# YouHaveBeenBlinded.net
KiCad netlist of a schematic drawn in EAGLE
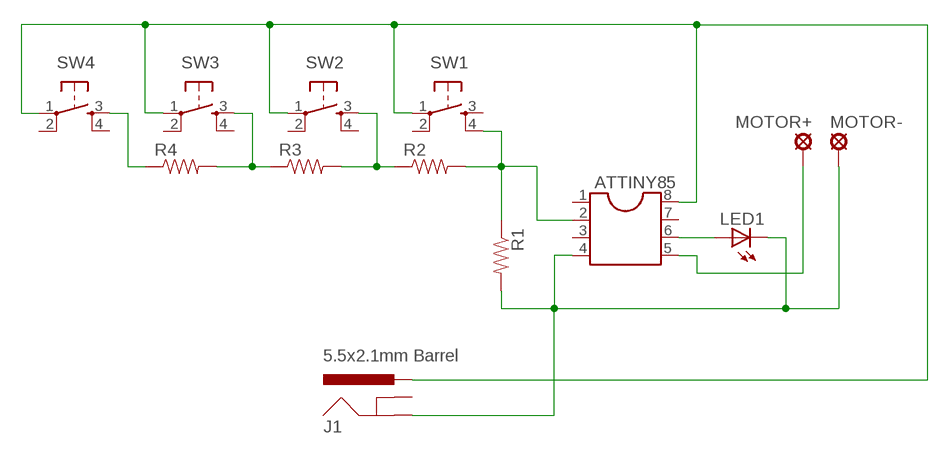
[diagram p0: schematic, sheet 1]

(export (version "E")
  (design (tool "Eeschema 10.0.6"))
  (components
    (comp (ref "ATTINY85")
      (value "DIL8S")
      (footprint "eagle-import:SOCKET-08")
      (libsource (lib "eagle-import") (part "DIL8S"))
    )
    (comp (ref "J1")
      (value "5.5x2.1mm Barrel")
      (footprint "eagle-import:POWER_JACK_SMD")
      (libsource (lib "eagle-import") (part "POWER_JACKSMD"))
    )
    (comp (ref "LED1")
      (value "LEDCHIPLED_0805")
      (footprint "eagle-import:CHIPLED_0805")
      (libsource (lib "eagle-import") (part "LEDCHIPLED_0805"))
    )
    (comp (ref "MOTOR+")
      (value "LSP10")
      (footprint "eagle-import:LSP10")
      (libsource (lib "eagle-import") (part "LSP10"))
    )
    (comp (ref "MOTOR-")
      (value "LSP10")
      (footprint "eagle-import:LSP10")
      (libsource (lib "eagle-import") (part "LSP10"))
    )
    (comp (ref "R1")
      (value "RESISTOR2010")
      (footprint "eagle-import:R2010")
      (libsource (lib "eagle-import") (part "RESISTOR2010"))
    )
    (comp (ref "R2")
      (value "RESISTOR2010")
      (footprint "eagle-import:R2010")
      (libsource (lib "eagle-import") (part "RESISTOR2010"))
    )
    (comp (ref "R3")
      (value "RESISTOR2010")
      (footprint "eagle-import:R2010")
      (libsource (lib "eagle-import") (part "RESISTOR2010"))
    )
    (comp (ref "R4")
      (value "RESISTOR2010")
      (footprint "eagle-import:R2010")
      (libsource (lib "eagle-import") (part "RESISTOR2010"))
    )
    (comp (ref "SW1")
      (value "TAC_SWITCHPTH")
      (footprint "eagle-import:TACTILE-PTH")
      (libsource (lib "eagle-import") (part "TAC_SWITCHPTH"))
    )
    (comp (ref "SW2")
      (value "TAC_SWITCHPTH")
      (footprint "eagle-import:TACTILE-PTH")
      (libsource (lib "eagle-import") (part "TAC_SWITCHPTH"))
    )
    (comp (ref "SW3")
      (value "TAC_SWITCHPTH")
      (footprint "eagle-import:TACTILE-PTH")
      (libsource (lib "eagle-import") (part "TAC_SWITCHPTH"))
    )
    (comp (ref "SW4")
      (value "TAC_SWITCHPTH")
      (footprint "eagle-import:TACTILE-PTH")
      (libsource (lib "eagle-import") (part "TAC_SWITCHPTH"))
    )
  )
  (nets
    (net (code "1") (name "Net-(ATTINY85-Pad2)") (class "Default")
      (node (ref "ATTINY85") (pin "2") (pinfunction "2_2") (pintype "passive"))
      (node (ref "R1") (pin "1") (pinfunction "1_1") (pintype "passive"))
      (node (ref "R2") (pin "2") (pinfunction "2_2") (pintype "passive"))
      (node (ref "SW1") (pin "4") (pinfunction "4_4") (pintype "passive"))
    )
    (net (code "2") (name "Net-(ATTINY85-Pad5)") (class "Default")
      (node (ref "ATTINY85") (pin "5") (pinfunction "5_5") (pintype "passive"))
      (node (ref "MOTOR+") (pin "MP") (pinfunction "MP_MP") (pintype "passive"))
    )
    (net (code "3") (name "Net-(ATTINY85-Pad6)") (class "Default")
      (node (ref "ATTINY85") (pin "6") (pinfunction "6_6") (pintype "passive"))
      (node (ref "LED1") (pin "A") (pinfunction "A_A") (pintype "passive"))
    )
    (net (code "4") (name "Net-(J1-GND)") (class "Default")
      (node (ref "ATTINY85") (pin "4") (pinfunction "4_4") (pintype "passive"))
      (node (ref "J1") (pin "P$4") (pinfunction "GND_P$4") (pintype "bidirectional"))
      (node (ref "LED1") (pin "C") (pinfunction "C_C") (pintype "passive"))
      (node (ref "MOTOR-") (pin "MP") (pinfunction "MP_MP") (pintype "passive"))
      (node (ref "R1") (pin "2") (pinfunction "2_2") (pintype "passive"))
    )
    (net (code "5") (name "Net-(J1-PWR)") (class "Default")
      (node (ref "ATTINY85") (pin "8") (pinfunction "8_8") (pintype "passive"))
      (node (ref "J1") (pin "VIN0") (pinfunction "PWR_VIN0") (pintype "bidirectional"))
      (node (ref "SW1") (pin "1") (pinfunction "1_1") (pintype "passive"))
      (node (ref "SW2") (pin "1") (pinfunction "1_1") (pintype "passive"))
      (node (ref "SW3") (pin "1") (pinfunction "1_1") (pintype "passive"))
      (node (ref "SW4") (pin "1") (pinfunction "1_1") (pintype "passive"))
    )
    (net (code "6") (name "Net-(R2-Pad1)") (class "Default")
      (node (ref "R2") (pin "1") (pinfunction "1_1") (pintype "passive"))
      (node (ref "R3") (pin "2") (pinfunction "2_2") (pintype "passive"))
      (node (ref "SW2") (pin "3") (pinfunction "3_3") (pintype "passive"))
    )
    (net (code "7") (name "Net-(R3-Pad1)") (class "Default")
      (node (ref "R3") (pin "1") (pinfunction "1_1") (pintype "passive"))
      (node (ref "R4") (pin "2") (pinfunction "2_2") (pintype "passive"))
      (node (ref "SW3") (pin "3") (pinfunction "3_3") (pintype "passive"))
    )
    (net (code "8") (name "Net-(R4-Pad1)") (class "Default")
      (node (ref "R4") (pin "1") (pinfunction "1_1") (pintype "passive"))
      (node (ref "SW4") (pin "3") (pinfunction "3_3") (pintype "passive"))
    )
    (net (code "9") (name "unconnected-(ATTINY85-Pad1)") (class "Default")
      (node (ref "ATTINY85") (pin "1") (pinfunction "1_1") (pintype "passive"))
    )
    (net (code "10") (name "unconnected-(ATTINY85-Pad3)") (class "Default")
      (node (ref "ATTINY85") (pin "3") (pinfunction "3_3") (pintype "passive"))
    )
    (net (code "11") (name "unconnected-(ATTINY85-Pad7)") (class "Default")
      (node (ref "ATTINY85") (pin "7") (pinfunction "7_7") (pintype "passive"))
    )
    (net (code "12") (name "unconnected-(J1-GNDBREAK-PadGND)") (class "Default")
      (node (ref "J1") (pin "GND") (pinfunction "GNDBREAK_GND") (pintype "bidirectional"))
    )
    (net (code "13") (name "unconnected-(SW1-Pad2)") (class "Default")
      (node (ref "SW1") (pin "2") (pinfunction "2_2") (pintype "passive"))
    )
    (net (code "14") (name "unconnected-(SW1-Pad3)") (class "Default")
      (node (ref "SW1") (pin "3") (pinfunction "3_3") (pintype "passive"))
    )
    (net (code "15") (name "unconnected-(SW2-Pad2)") (class "Default")
      (node (ref "SW2") (pin "2") (pinfunction "2_2") (pintype "passive"))
    )
    (net (code "16") (name "unconnected-(SW2-Pad4)") (class "Default")
      (node (ref "SW2") (pin "4") (pinfunction "4_4") (pintype "passive"))
    )
    (net (code "17") (name "unconnected-(SW3-Pad2)") (class "Default")
      (node (ref "SW3") (pin "2") (pinfunction "2_2") (pintype "passive"))
    )
    (net (code "18") (name "unconnected-(SW3-Pad4)") (class "Default")
      (node (ref "SW3") (pin "4") (pinfunction "4_4") (pintype "passive"))
    )
    (net (code "19") (name "unconnected-(SW4-Pad2)") (class "Default")
      (node (ref "SW4") (pin "2") (pinfunction "2_2") (pintype "passive"))
    )
    (net (code "20") (name "unconnected-(SW4-Pad4)") (class "Default")
      (node (ref "SW4") (pin "4") (pinfunction "4_4") (pintype "passive"))
    )
  )
)
